# GPIO.net
KiCad netlist of a schematic drawn in Altium Designer
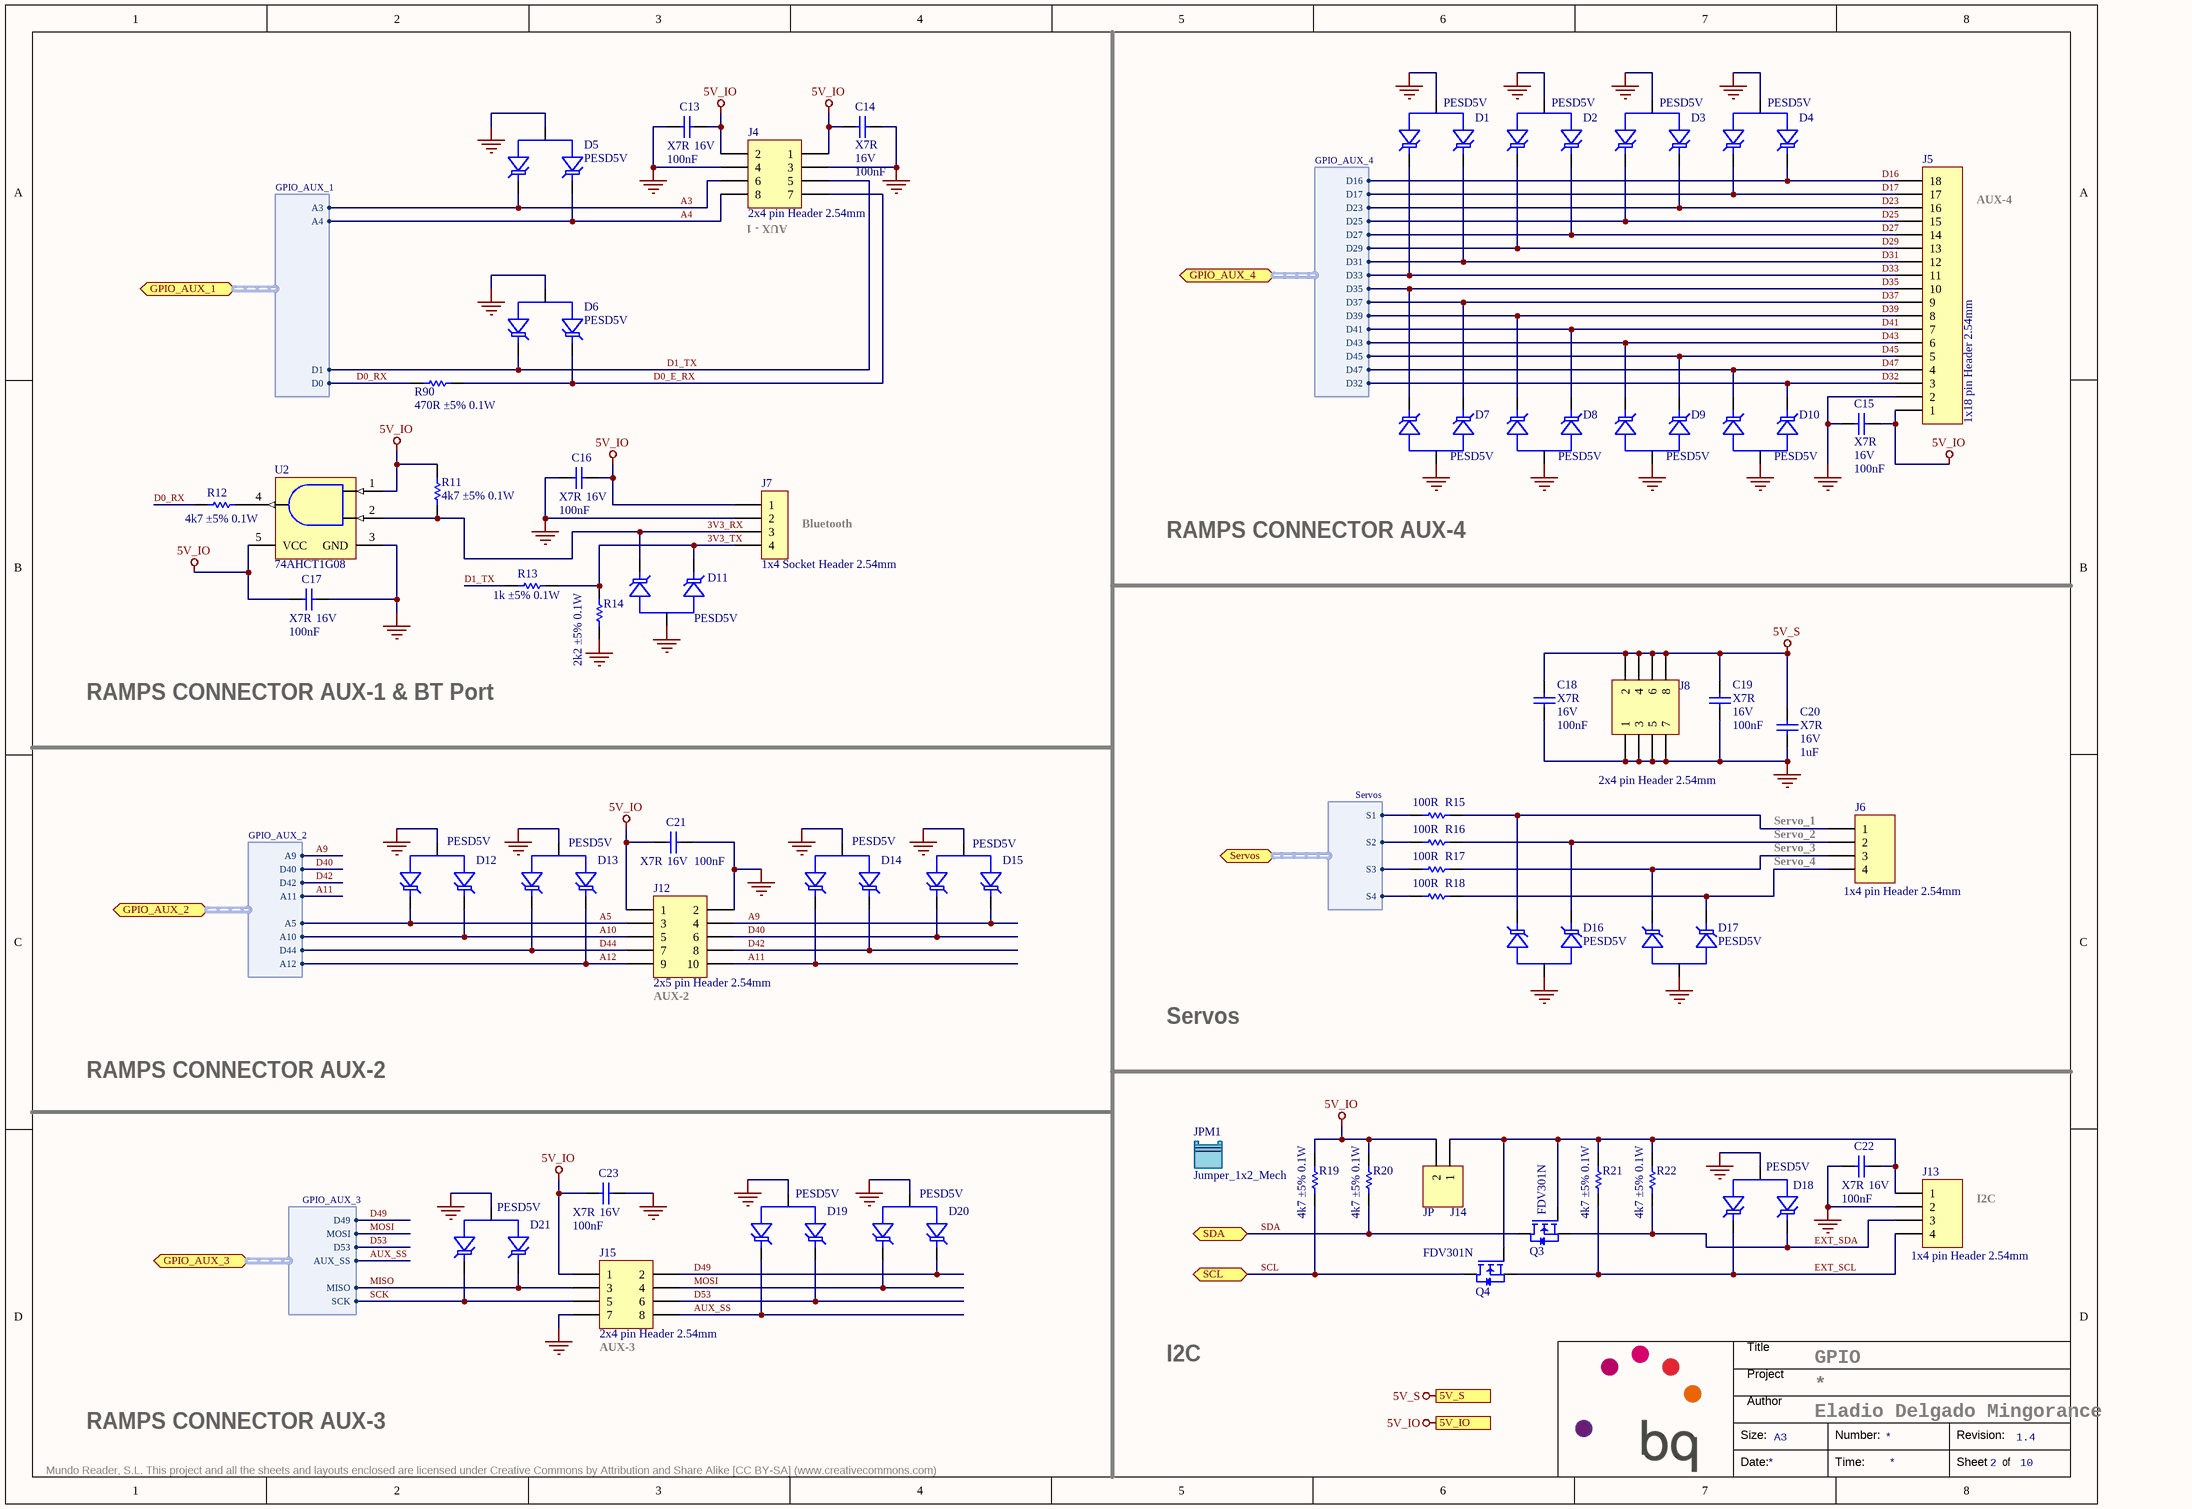
[diagram p0: GPIO.SchDoc]

(export (version "E")
  (design (tool "Eeschema 10.0.6"))
  (components
    (comp (ref "C13")
      (value "Capacitor")
      (footprint "C0603")
      (fields
        (field (name "DIELECTRIC") "X7R")
        (field (name "VOLTAGE") "16V")
        (field (name "CAPACITANCE") "100nF")
        (field (name "PART NUMBER") "C0603_100nF_16V_±10%")
        (field (name "TOLERANCE") "±10%")
        (field (name "MANUFACTURER") "Kemet")
      )
      (libsource (lib "Pasives_Capacitor_SMD") (part "Capacitor"))
    )
    (comp (ref "C14")
      (value "Capacitor")
      (footprint "C0603")
      (fields
        (field (name "DIELECTRIC") "X7R")
        (field (name "VOLTAGE") "16V")
        (field (name "CAPACITANCE") "100nF")
        (field (name "PART NUMBER") "C0603_100nF_16V_±10%")
        (field (name "TOLERANCE") "±10%")
        (field (name "MANUFACTURER") "Kemet")
      )
      (libsource (lib "Pasives_Capacitor_SMD") (part "Capacitor"))
    )
    (comp (ref "C15")
      (value "Capacitor")
      (footprint "C0603")
      (fields
        (field (name "DIELECTRIC") "X7R")
        (field (name "VOLTAGE") "16V")
        (field (name "CAPACITANCE") "100nF")
        (field (name "PART NUMBER") "C0603_100nF_16V_±10%")
        (field (name "TOLERANCE") "±10%")
        (field (name "MANUFACTURER") "Kemet")
      )
      (libsource (lib "Pasives_Capacitor_SMD") (part "Capacitor"))
    )
    (comp (ref "C16")
      (value "Capacitor")
      (footprint "C0603")
      (fields
        (field (name "DIELECTRIC") "X7R")
        (field (name "VOLTAGE") "16V")
        (field (name "CAPACITANCE") "100nF")
        (field (name "PART NUMBER") "C0603_100nF_16V_±10%")
        (field (name "TOLERANCE") "±10%")
        (field (name "MANUFACTURER") "Kemet")
      )
      (libsource (lib "Pasives_Capacitor_SMD") (part "Capacitor"))
    )
    (comp (ref "C17")
      (value "Capacitor")
      (footprint "C0603")
      (fields
        (field (name "DIELECTRIC") "X7R")
        (field (name "VOLTAGE") "16V")
        (field (name "CAPACITANCE") "100nF")
        (field (name "PART NUMBER") "C0603_100nF_16V_±10%")
        (field (name "TOLERANCE") "±10%")
        (field (name "MANUFACTURER") "Kemet")
      )
      (libsource (lib "Pasives_Capacitor_SMD") (part "Capacitor"))
    )
    (comp (ref "C18")
      (value "Capacitor")
      (footprint "C0603")
      (fields
        (field (name "DIELECTRIC") "X7R")
        (field (name "VOLTAGE") "16V")
        (field (name "CAPACITANCE") "100nF")
        (field (name "PART NUMBER") "C0603_100nF_16V_±10%")
        (field (name "TOLERANCE") "±10%")
        (field (name "MANUFACTURER") "Kemet")
      )
      (libsource (lib "Pasives_Capacitor_SMD") (part "Capacitor"))
    )
    (comp (ref "C19")
      (value "Capacitor")
      (footprint "C0603")
      (fields
        (field (name "DIELECTRIC") "X7R")
        (field (name "VOLTAGE") "16V")
        (field (name "CAPACITANCE") "100nF")
        (field (name "PART NUMBER") "C0603_100nF_16V_±10%")
        (field (name "TOLERANCE") "±10%")
        (field (name "MANUFACTURER") "Kemet")
      )
      (libsource (lib "Pasives_Capacitor_SMD") (part "Capacitor"))
    )
    (comp (ref "C20")
      (value "Capacitor")
      (footprint "C0603")
      (fields
        (field (name "DIELECTRIC") "X7R")
        (field (name "VOLTAGE") "16V")
        (field (name "CAPACITANCE") "1uF")
        (field (name "PART NUMBER") "C0603_1uF_16V_±10%_X7R")
        (field (name "TOLERANCE") "±10%")
        (field (name "MANUFACTURER") "TDK")
      )
      (libsource (lib "Pasives_Capacitor_SMD") (part "Capacitor"))
    )
    (comp (ref "C21")
      (value "Capacitor")
      (footprint "C0603")
      (fields
        (field (name "DIELECTRIC") "X7R")
        (field (name "VOLTAGE") "16V")
        (field (name "CAPACITANCE") "100nF")
        (field (name "PART NUMBER") "C0603_100nF_16V_±10%")
        (field (name "TOLERANCE") "±10%")
        (field (name "MANUFACTURER") "Kemet")
      )
      (libsource (lib "Pasives_Capacitor_SMD") (part "Capacitor"))
    )
    (comp (ref "C22")
      (value "Capacitor")
      (footprint "C0603")
      (fields
        (field (name "DIELECTRIC") "X7R")
        (field (name "VOLTAGE") "16V")
        (field (name "CAPACITANCE") "100nF")
        (field (name "PART NUMBER") "C0603_100nF_16V_±10%")
        (field (name "TOLERANCE") "±10%")
        (field (name "MANUFACTURER") "Kemet")
      )
      (libsource (lib "Pasives_Capacitor_SMD") (part "Capacitor"))
    )
    (comp (ref "C23")
      (value "Capacitor")
      (footprint "C0603")
      (fields
        (field (name "DIELECTRIC") "X7R")
        (field (name "VOLTAGE") "16V")
        (field (name "CAPACITANCE") "100nF")
        (field (name "PART NUMBER") "C0603_100nF_16V_±10%")
        (field (name "TOLERANCE") "±10%")
        (field (name "MANUFACTURER") "Kemet")
      )
      (libsource (lib "Pasives_Capacitor_SMD") (part "Capacitor"))
    )
    (comp (ref "D1")
      (value "PESD5V")
      (footprint "SOT323_3_SC70")
      (description "Dual ESD protection diode")
      (fields (field (name "MANUFACTURER") "NXP"))
      (libsource (lib "Protection") (part "ESD_Dual_Diode"))
    )
    (comp (ref "D2")
      (value "PESD5V")
      (footprint "SOT323_3_SC70")
      (description "Dual ESD protection diode")
      (fields (field (name "MANUFACTURER") "NXP"))
      (libsource (lib "Protection") (part "ESD_Dual_Diode"))
    )
    (comp (ref "D3")
      (value "PESD5V")
      (footprint "SOT323_3_SC70")
      (description "Dual ESD protection diode")
      (fields (field (name "MANUFACTURER") "NXP"))
      (libsource (lib "Protection") (part "ESD_Dual_Diode"))
    )
    (comp (ref "D4")
      (value "PESD5V")
      (footprint "SOT323_3_SC70")
      (description "Dual ESD protection diode")
      (fields (field (name "MANUFACTURER") "NXP"))
      (libsource (lib "Protection") (part "ESD_Dual_Diode"))
    )
    (comp (ref "D5")
      (value "PESD5V")
      (footprint "SOT323_3_SC70")
      (description "Dual ESD protection diode")
      (fields (field (name "MANUFACTURER") "NXP"))
      (libsource (lib "Protection") (part "ESD_Dual_Diode"))
    )
    (comp (ref "D6")
      (value "PESD5V")
      (footprint "SOT323_3_SC70")
      (description "Dual ESD protection diode")
      (fields (field (name "MANUFACTURER") "NXP"))
      (libsource (lib "Protection") (part "ESD_Dual_Diode"))
    )
    (comp (ref "D7")
      (value "PESD5V")
      (footprint "SOT323_3_SC70")
      (description "Dual ESD protection diode")
      (fields (field (name "MANUFACTURER") "NXP"))
      (libsource (lib "Protection") (part "ESD_Dual_Diode"))
    )
    (comp (ref "D8")
      (value "PESD5V")
      (footprint "SOT323_3_SC70")
      (description "Dual ESD protection diode")
      (fields (field (name "MANUFACTURER") "NXP"))
      (libsource (lib "Protection") (part "ESD_Dual_Diode"))
    )
    (comp (ref "D9")
      (value "PESD5V")
      (footprint "SOT323_3_SC70")
      (description "Dual ESD protection diode")
      (fields (field (name "MANUFACTURER") "NXP"))
      (libsource (lib "Protection") (part "ESD_Dual_Diode"))
    )
    (comp (ref "D10")
      (value "PESD5V")
      (footprint "SOT323_3_SC70")
      (description "Dual ESD protection diode")
      (fields (field (name "MANUFACTURER") "NXP"))
      (libsource (lib "Protection") (part "ESD_Dual_Diode"))
    )
    (comp (ref "D11")
      (value "PESD5V")
      (footprint "SOT323_3_SC70")
      (description "Dual ESD protection diode")
      (fields (field (name "MANUFACTURER") "NXP"))
      (libsource (lib "Protection") (part "ESD_Dual_Diode"))
    )
    (comp (ref "D12")
      (value "PESD5V")
      (footprint "SOT323_3_SC70")
      (description "Dual ESD protection diode")
      (fields (field (name "MANUFACTURER") "NXP"))
      (libsource (lib "Protection") (part "ESD_Dual_Diode"))
    )
    (comp (ref "D13")
      (value "PESD5V")
      (footprint "SOT323_3_SC70")
      (description "Dual ESD protection diode")
      (fields (field (name "MANUFACTURER") "NXP"))
      (libsource (lib "Protection") (part "ESD_Dual_Diode"))
    )
    (comp (ref "D14")
      (value "PESD5V")
      (footprint "SOT323_3_SC70")
      (description "Dual ESD protection diode")
      (fields (field (name "MANUFACTURER") "NXP"))
      (libsource (lib "Protection") (part "ESD_Dual_Diode"))
    )
    (comp (ref "D15")
      (value "PESD5V")
      (footprint "SOT323_3_SC70")
      (description "Dual ESD protection diode")
      (fields (field (name "MANUFACTURER") "NXP"))
      (libsource (lib "Protection") (part "ESD_Dual_Diode"))
    )
    (comp (ref "D16")
      (value "PESD5V")
      (footprint "SOT323_3_SC70")
      (description "Dual ESD protection diode")
      (fields (field (name "MANUFACTURER") "NXP"))
      (libsource (lib "Protection") (part "ESD_Dual_Diode"))
    )
    (comp (ref "D17")
      (value "PESD5V")
      (footprint "SOT323_3_SC70")
      (description "Dual ESD protection diode")
      (fields (field (name "MANUFACTURER") "NXP"))
      (libsource (lib "Protection") (part "ESD_Dual_Diode"))
    )
    (comp (ref "D18")
      (value "PESD5V")
      (footprint "SOT323_3_SC70")
      (description "Dual ESD protection diode")
      (fields (field (name "MANUFACTURER") "NXP"))
      (libsource (lib "Protection") (part "ESD_Dual_Diode"))
    )
    (comp (ref "D19")
      (value "PESD5V")
      (footprint "SOT323_3_SC70")
      (description "Dual ESD protection diode")
      (fields (field (name "MANUFACTURER") "NXP"))
      (libsource (lib "Protection") (part "ESD_Dual_Diode"))
    )
    (comp (ref "D20")
      (value "PESD5V")
      (footprint "SOT323_3_SC70")
      (description "Dual ESD protection diode")
      (fields (field (name "MANUFACTURER") "NXP"))
      (libsource (lib "Protection") (part "ESD_Dual_Diode"))
    )
    (comp (ref "D21")
      (value "PESD5V")
      (footprint "SOT323_3_SC70")
      (description "Dual ESD protection diode")
      (fields (field (name "MANUFACTURER") "NXP"))
      (libsource (lib "Protection") (part "ESD_Dual_Diode"))
    )
    (comp (ref "J4")
      (value "2x4 pin Header 2.54mm")
      (footprint "2x4 Pin Header 2.54")
      (description "Connector, 8 pin Dual Header 2.54mm")
      (fields (field (name "MANUFACTURER") "Samtec") (field (name "PART NUMBER") "CON_DPH_THT2.54_8"))
      (libsource (lib "") (part "2x4 pin Header 2.54mm_2"))
    )
    (comp (ref "J5")
      (value "1x18 pin Header 2.54mm")
      (footprint "1x18 Pin Header 2.54")
      (fields (field (name "MANUFACTURER") "Samtec") (field (name "PART NUMBER") "CON_PH_THT2.54_18"))
      (libsource (lib "Conectores_PinHeader_2.54") (part "1x18 pin Header 2.54mm"))
    )
    (comp (ref "J6")
      (value "1x4 pin Header 2.54mm")
      (footprint "1x4 Pin Header 2.54")
      (fields (field (name "MANUFACTURER") "Samtec") (field (name "PART NUMBER") "CON_PH_THT2.54_4"))
      (libsource (lib "Conectores_PinHeader_2.54") (part "1x4 pin Header 2.54mm"))
    )
    (comp (ref "J7")
      (value "1x4 Socket Header 2.54mm")
      (footprint "1x4 Socket Header THT 2.54mm")
      (description "4 pin Socket Header 2.54mm")
      (fields (field (name "PART NUMBER") "CON_SH_THT2.54_4") (field (name "MANUFACTURER") "Samtec"))
      (libsource (lib "Conectores_SocketHeader_2.54") (part "1x4 Socket Header 2.54mm"))
    )
    (comp (ref "J8")
      (value "2x4 pin Header 2.54mm")
      (footprint "2x4 Pin Header 2.54")
      (description "Connector, 8 pin Dual Header 2.54mm")
      (fields (field (name "MANUFACTURER") "Samtec") (field (name "PART NUMBER") "CON_DPH_THT2.54_8"))
      (libsource (lib "") (part "2x4 pin Header 2.54mm_1"))
    )
    (comp (ref "J12")
      (value "2x5 pin Header 2.54mm")
      (footprint "2x5 Pin Header 2.54")
      (description "10 pin Dual Header 2.54mm")
      (fields (field (name "MANUFACTURER") "Samtec") (field (name "PART NUMBER") "CON_DPH_THT2.54_10"))
      (libsource (lib "Conectores_PinHeader_2.54") (part "2x5 pin Header 2.54mm"))
    )
    (comp (ref "J13")
      (value "1x4 pin Header 2.54mm")
      (footprint "1x4 Pin Header 2.54")
      (fields (field (name "MANUFACTURER") "Samtec") (field (name "PART NUMBER") "CON_PH_THT2.54_4"))
      (libsource (lib "Conectores_PinHeader_2.54") (part "1x4 pin Header 2.54mm"))
    )
    (comp (ref "J14")
      (value "JP")
      (footprint "1x2 Pin Header 2.54")
      (description "1x2 pin Header 2.54mm")
      (fields (field (name "PART NUMBER") "CON_PH_THT2.54_2") (field (name "MANUFACTURER") "Samtec"))
      (libsource (lib "Conectores_PinHeader_2.54") (part "1x2 pin Header 2.54mm"))
    )
    (comp (ref "J15")
      (value "2x4 pin Header 2.54mm")
      (footprint "2x4 Pin Header 2.54")
      (description "8 pin Dual Header 2.54mm")
      (fields (field (name "MANUFACTURER") "Samtec") (field (name "PART NUMBER") "CON_DPH_THT2.54_8"))
      (libsource (lib "Conectores_PinHeader_2.54") (part "2x4 pin Header 2.54mm"))
    )
    (comp (ref "JPM1")
      (value "Jumper_1x2_Mech")
      (description "Connector, Jumper, 1x2 Jumper 2.54mm")
      (fields (field (name "PART NUMBER") "Jumper_2pin_Mech") (field (name "MANUFACTURER") "Würth"))
      (libsource (lib "Connectors_Jumpers") (part "Jumper_1x2_Mech"))
    )
    (comp (ref "Q3")
      (value "FDV301N")
      (footprint "SOT23-3")
      (description "Mosfet Channel N Enhancement Mode")
      (fields (field (name "MANUFACTURER") "Fairchild Semiconductor"))
      (libsource (lib "Semiconductors_Transistors") (part "Mosfet_N"))
    )
    (comp (ref "Q4")
      (value "FDV301N")
      (footprint "SOT23-3")
      (description "Mosfet Channel N Enhancement Mode")
      (fields (field (name "MANUFACTURER") "Fairchild Semiconductor"))
      (libsource (lib "Semiconductors_Transistors") (part "Mosfet_N"))
    )
    (comp (ref "R11")
      (value "4k7 ±5% 0.1W")
      (footprint "R0603")
      (description "Resistor, SMD")
      (fields (field (name "TOLERANCE") "±5%") (field (name "POWER") "0.1W"))
      (libsource (lib "Pasives_Resistor_SMD") (part "Resistor"))
    )
    (comp (ref "R12")
      (value "4k7 ±5% 0.1W")
      (footprint "R0603")
      (description "Resistor")
      (fields (field (name "TOLERANCE") "±5%") (field (name "POWER") "0.1W"))
      (libsource (lib "Pasives_Resistor_SMD") (part "Resistor"))
    )
    (comp (ref "R13")
      (value "1k ±5% 0.1W")
      (footprint "R0603")
      (description "Resistor")
      (fields (field (name "TOLERANCE") "±5%") (field (name "POWER") "0.1W"))
      (libsource (lib "Pasives_Resistor_SMD") (part "Resistor"))
    )
    (comp (ref "R14")
      (value "2k2 ±5% 0.1W")
      (footprint "R0603")
      (description "Resistor")
      (fields (field (name "TOLERANCE") "±5%") (field (name "POWER") "0.1W"))
      (libsource (lib "Pasives_Resistor_SMD") (part "Resistor"))
    )
    (comp (ref "R15")
      (value "~")
      (footprint "R0603")
      (description "Resistor")
      (fields
        (field (name "TOLERANCE") "±5%")
        (field (name "POWER") "0.1W")
        (field (name "RESISTANCE") "100R")
      )
      (libsource (lib "Pasives_Resistor_SMD") (part "Resistor"))
    )
    (comp (ref "R16")
      (value "~")
      (footprint "R0603")
      (description "Resistor")
      (fields
        (field (name "TOLERANCE") "±5%")
        (field (name "POWER") "0.1W")
        (field (name "RESISTANCE") "100R")
      )
      (libsource (lib "Pasives_Resistor_SMD") (part "Resistor"))
    )
    (comp (ref "R17")
      (value "~")
      (footprint "R0603")
      (description "Resistor")
      (fields
        (field (name "TOLERANCE") "±5%")
        (field (name "POWER") "0.1W")
        (field (name "RESISTANCE") "100R")
      )
      (libsource (lib "Pasives_Resistor_SMD") (part "Resistor"))
    )
    (comp (ref "R18")
      (value "~")
      (footprint "R0603")
      (description "Resistor")
      (fields
        (field (name "TOLERANCE") "±5%")
        (field (name "POWER") "0.1W")
        (field (name "RESISTANCE") "100R")
      )
      (libsource (lib "Pasives_Resistor_SMD") (part "Resistor"))
    )
    (comp (ref "R19")
      (value "4k7 ±5% 0.1W")
      (footprint "R0603")
      (description "Resistor")
      (fields (field (name "TOLERANCE") "±5%") (field (name "POWER") "0.1W"))
      (libsource (lib "Pasives_Resistor_SMD") (part "Resistor"))
    )
    (comp (ref "R20")
      (value "4k7 ±5% 0.1W")
      (footprint "R0603")
      (description "Resistor")
      (fields (field (name "TOLERANCE") "±5%") (field (name "POWER") "0.1W"))
      (libsource (lib "Pasives_Resistor_SMD") (part "Resistor"))
    )
    (comp (ref "R21")
      (value "4k7 ±5% 0.1W")
      (footprint "R0603")
      (description "Resistor")
      (fields (field (name "TOLERANCE") "±5%") (field (name "POWER") "0.1W"))
      (libsource (lib "Pasives_Resistor_SMD") (part "Resistor"))
    )
    (comp (ref "R22")
      (value "4k7 ±5% 0.1W")
      (footprint "R0603")
      (description "Resistor")
      (fields (field (name "TOLERANCE") "±5%") (field (name "POWER") "0.1W"))
      (libsource (lib "Pasives_Resistor_SMD") (part "Resistor"))
    )
    (comp (ref "R90")
      (value "470R ±5% 0.1W")
      (footprint "R0603")
      (description "Resistor, SMD")
      (fields (field (name "TOLERANCE") "±5%") (field (name "POWER") "0.1W"))
      (libsource (lib "Pasives_Resistor_SMD") (part "Resistor"))
    )
    (comp (ref "U2")
      (value "74AHCT1G08")
      (footprint "SOT23-5")
      (description "Dual AND Gate Single Ouput")
      (fields (field (name "PART NUMBER") "SN74AHCT1G08") (field (name "MANUFACTURER") "Texas Instruments"))
      (libsource (lib "Semiconductors_Logic_Gate") (part "AND_2I_1O"))
    )
  )
  (nets
    (net (code "6") (name "/3V3_RX") (class "Default")
      (node (ref "D11") (pin "2") (pinfunction "2_2") (pintype "passive"))
      (node (ref "J7") (pin "3") (pinfunction "3_3") (pintype "passive"))
      (node (ref "R11") (pin "1") (pinfunction "1_1") (pintype "passive"))
      (node (ref "U2") (pin "2") (pinfunction "B_2") (pintype "input"))
    )
    (net (code "7") (name "/3V3_TX") (class "Default")
      (node (ref "D11") (pin "1") (pinfunction "1_1") (pintype "passive"))
      (node (ref "J7") (pin "4") (pinfunction "4_4") (pintype "passive"))
      (node (ref "R13") (pin "2") (pinfunction "2_2") (pintype "passive"))
      (node (ref "R14") (pin "2") (pinfunction "2_2") (pintype "passive"))
    )
    (net (code "8") (name "/A3") (class "Default")
      (node (ref "D5") (pin "1") (pinfunction "1_1") (pintype "passive"))
      (node (ref "J4") (pin "6") (pinfunction "6_6") (pintype "passive"))
    )
    (net (code "9") (name "/A4") (class "Default")
      (node (ref "D5") (pin "2") (pinfunction "2_2") (pintype "passive"))
      (node (ref "J4") (pin "8") (pinfunction "8_8") (pintype "passive"))
    )
    (net (code "10") (name "/A5") (class "Default")
      (node (ref "D12") (pin "2") (pinfunction "2_2") (pintype "passive"))
      (node (ref "J12") (pin "3") (pinfunction "3_3") (pintype "passive"))
    )
    (net (code "11") (name "/A9") (class "Default")
      (node (ref "D15") (pin "1") (pinfunction "1_1") (pintype "passive"))
      (node (ref "J12") (pin "4") (pinfunction "4_4") (pintype "passive"))
    )
    (net (code "12") (name "/A10") (class "Default")
      (node (ref "D12") (pin "1") (pinfunction "1_1") (pintype "passive"))
      (node (ref "J12") (pin "5") (pinfunction "5_5") (pintype "passive"))
    )
    (net (code "13") (name "/A11") (class "Default")
      (node (ref "D14") (pin "2") (pinfunction "2_2") (pintype "passive"))
      (node (ref "J12") (pin "10") (pinfunction "10_10") (pintype "passive"))
    )
    (net (code "14") (name "/A12") (class "Default")
      (node (ref "D13") (pin "1") (pinfunction "1_1") (pintype "passive"))
      (node (ref "J12") (pin "9") (pinfunction "9_9") (pintype "passive"))
    )
    (net (code "15") (name "/AUX_SS") (class "Default")
      (node (ref "D19") (pin "2") (pinfunction "2_2") (pintype "passive"))
      (node (ref "J15") (pin "8") (pinfunction "8_8") (pintype "passive"))
    )
    (net (code "16") (name "/D0_E_RX") (class "Default")
      (node (ref "D6") (pin "1") (pinfunction "1_1") (pintype "passive"))
      (node (ref "J4") (pin "7") (pinfunction "7_7") (pintype "passive"))
      (node (ref "R90") (pin "1") (pinfunction "1_1") (pintype "passive"))
    )
    (net (code "17") (name "/D0_RX") (class "Default")
      (node (ref "R12") (pin "2") (pinfunction "2_2") (pintype "passive"))
      (node (ref "R90") (pin "2") (pinfunction "2_2") (pintype "passive"))
    )
    (net (code "18") (name "/D1_TX") (class "Default")
      (node (ref "D6") (pin "2") (pinfunction "2_2") (pintype "passive"))
      (node (ref "J4") (pin "5") (pinfunction "5_5") (pintype "passive"))
      (node (ref "R13") (pin "1") (pinfunction "1_1") (pintype "passive"))
    )
    (net (code "19") (name "/D16") (class "Default")
      (node (ref "D4") (pin "2") (pinfunction "2_2") (pintype "passive"))
      (node (ref "J5") (pin "18") (pinfunction "18_18") (pintype "passive"))
    )
    (net (code "20") (name "/D17") (class "Default")
      (node (ref "D4") (pin "1") (pinfunction "1_1") (pintype "passive"))
      (node (ref "J5") (pin "17") (pinfunction "17_17") (pintype "passive"))
    )
    (net (code "21") (name "/D23") (class "Default")
      (node (ref "D3") (pin "2") (pinfunction "2_2") (pintype "passive"))
      (node (ref "J5") (pin "16") (pinfunction "16_16") (pintype "passive"))
    )
    (net (code "22") (name "/D25") (class "Default")
      (node (ref "D3") (pin "1") (pinfunction "1_1") (pintype "passive"))
      (node (ref "J5") (pin "15") (pinfunction "15_15") (pintype "passive"))
    )
    (net (code "23") (name "/D27") (class "Default")
      (node (ref "D2") (pin "2") (pinfunction "2_2") (pintype "passive"))
      (node (ref "J5") (pin "14") (pinfunction "14_14") (pintype "passive"))
    )
    (net (code "24") (name "/D29") (class "Default")
      (node (ref "D2") (pin "1") (pinfunction "1_1") (pintype "passive"))
      (node (ref "J5") (pin "13") (pinfunction "13_13") (pintype "passive"))
    )
    (net (code "25") (name "/D31") (class "Default")
      (node (ref "D1") (pin "2") (pinfunction "2_2") (pintype "passive"))
      (node (ref "J5") (pin "12") (pinfunction "12_12") (pintype "passive"))
    )
    (net (code "26") (name "/D32") (class "Default")
      (node (ref "D10") (pin "1") (pinfunction "1_1") (pintype "passive"))
      (node (ref "J5") (pin "3") (pinfunction "3_3") (pintype "passive"))
    )
    (net (code "27") (name "/D33") (class "Default")
      (node (ref "D1") (pin "1") (pinfunction "1_1") (pintype "passive"))
      (node (ref "J5") (pin "11") (pinfunction "11_11") (pintype "passive"))
    )
    (net (code "28") (name "/D35") (class "Default")
      (node (ref "D7") (pin "2") (pinfunction "2_2") (pintype "passive"))
      (node (ref "J5") (pin "10") (pinfunction "10_10") (pintype "passive"))
    )
    (net (code "29") (name "/D37") (class "Default")
      (node (ref "D7") (pin "1") (pinfunction "1_1") (pintype "passive"))
      (node (ref "J5") (pin "9") (pinfunction "9_9") (pintype "passive"))
    )
    (net (code "30") (name "/D39") (class "Default")
      (node (ref "D8") (pin "2") (pinfunction "2_2") (pintype "passive"))
      (node (ref "J5") (pin "8") (pinfunction "8_8") (pintype "passive"))
    )
    (net (code "31") (name "/D40") (class "Default")
      (node (ref "D15") (pin "2") (pinfunction "2_2") (pintype "passive"))
      (node (ref "J12") (pin "6") (pinfunction "6_6") (pintype "passive"))
    )
    (net (code "32") (name "/D41") (class "Default")
      (node (ref "D8") (pin "1") (pinfunction "1_1") (pintype "passive"))
      (node (ref "J5") (pin "7") (pinfunction "7_7") (pintype "passive"))
    )
    (net (code "33") (name "/D42") (class "Default")
      (node (ref "D14") (pin "1") (pinfunction "1_1") (pintype "passive"))
      (node (ref "J12") (pin "8") (pinfunction "8_8") (pintype "passive"))
    )
    (net (code "34") (name "/D43") (class "Default")
      (node (ref "D9") (pin "2") (pinfunction "2_2") (pintype "passive"))
      (node (ref "J5") (pin "6") (pinfunction "6_6") (pintype "passive"))
    )
    (net (code "35") (name "/D44") (class "Default")
      (node (ref "D13") (pin "2") (pinfunction "2_2") (pintype "passive"))
      (node (ref "J12") (pin "7") (pinfunction "7_7") (pintype "passive"))
    )
    (net (code "36") (name "/D45") (class "Default")
      (node (ref "D9") (pin "1") (pinfunction "1_1") (pintype "passive"))
      (node (ref "J5") (pin "5") (pinfunction "5_5") (pintype "passive"))
    )
    (net (code "37") (name "/D47") (class "Default")
      (node (ref "D10") (pin "2") (pinfunction "2_2") (pintype "passive"))
      (node (ref "J5") (pin "4") (pinfunction "4_4") (pintype "passive"))
    )
    (net (code "38") (name "/D49") (class "Default")
      (node (ref "D20") (pin "1") (pinfunction "1_1") (pintype "passive"))
      (node (ref "J15") (pin "2") (pinfunction "2_2") (pintype "passive"))
    )
    (net (code "39") (name "/D53") (class "Default")
      (node (ref "D19") (pin "1") (pinfunction "1_1") (pintype "passive"))
      (node (ref "J15") (pin "6") (pinfunction "6_6") (pintype "passive"))
    )
    (net (code "40") (name "/EXT_SCL") (class "Default")
      (node (ref "D18") (pin "1") (pinfunction "1_1") (pintype "passive"))
      (node (ref "J13") (pin "4") (pinfunction "4_4") (pintype "passive"))
      (node (ref "Q4") (pin "2") (pinfunction "S_2") (pintype "passive"))
      (node (ref "R21") (pin "2") (pinfunction "2_2") (pintype "passive"))
    )
    (net (code "41") (name "/EXT_SDA") (class "Default")
      (node (ref "D18") (pin "2") (pinfunction "2_2") (pintype "passive"))
      (node (ref "J13") (pin "3") (pinfunction "3_3") (pintype "passive"))
      (node (ref "Q3") (pin "2") (pinfunction "S_2") (pintype "passive"))
      (node (ref "R22") (pin "2") (pinfunction "2_2") (pintype "passive"))
    )
    (net (code "42") (name "/MISO") (class "Default")
      (node (ref "D21") (pin "2") (pinfunction "2_2") (pintype "passive"))
      (node (ref "J15") (pin "3") (pinfunction "3_3") (pintype "passive"))
    )
    (net (code "43") (name "/MOSI") (class "Default")
      (node (ref "D20") (pin "2") (pinfunction "2_2") (pintype "passive"))
      (node (ref "J15") (pin "4") (pinfunction "4_4") (pintype "passive"))
    )
    (net (code "44") (name "/S1") (class "Default")
      (node (ref "R15") (pin "1") (pinfunction "1_1") (pintype "passive"))
    )
    (net (code "45") (name "/S2") (class "Default")
      (node (ref "R16") (pin "1") (pinfunction "1_1") (pintype "passive"))
    )
    (net (code "46") (name "/S3") (class "Default")
      (node (ref "R17") (pin "1") (pinfunction "1_1") (pintype "passive"))
    )
    (net (code "47") (name "/S4") (class "Default")
      (node (ref "R18") (pin "1") (pinfunction "1_1") (pintype "passive"))
    )
    (net (code "48") (name "/SCK") (class "Default")
      (node (ref "D21") (pin "1") (pinfunction "1_1") (pintype "passive"))
      (node (ref "J15") (pin "5") (pinfunction "5_5") (pintype "passive"))
    )
    (net (code "49") (name "/SCL") (class "Default")
      (node (ref "Q4") (pin "3") (pinfunction "D_3") (pintype "passive"))
      (node (ref "R19") (pin "2") (pinfunction "2_2") (pintype "passive"))
    )
    (net (code "50") (name "/SDA") (class "Default")
      (node (ref "Q3") (pin "3") (pinfunction "D_3") (pintype "passive"))
      (node (ref "R20") (pin "2") (pinfunction "2_2") (pintype "passive"))
    )
    (net (code "56") (name "5V_IO") (class "Default")
      (node (ref "C13") (pin "1") (pinfunction "1_1") (pintype "passive"))
      (node (ref "C14") (pin "1") (pinfunction "1_1") (pintype "passive"))
      (node (ref "C15") (pin "1") (pinfunction "1_1") (pintype "passive"))
      (node (ref "C16") (pin "1") (pinfunction "1_1") (pintype "passive"))
      (node (ref "C17") (pin "2") (pinfunction "2_2") (pintype "passive"))
      (node (ref "C21") (pin "2") (pinfunction "2_2") (pintype "passive"))
      (node (ref "C23") (pin "2") (pinfunction "2_2") (pintype "passive"))
      (node (ref "J12") (pin "1") (pinfunction "1_1") (pintype "passive"))
      (node (ref "J14") (pin "2") (pinfunction "2_2") (pintype "passive"))
      (node (ref "J15") (pin "1") (pinfunction "1_1") (pintype "passive"))
      (node (ref "J4") (pin "1") (pinfunction "1_1") (pintype "passive"))
      (node (ref "J4") (pin "2") (pinfunction "2_2") (pintype "passive"))
      (node (ref "J5") (pin "1") (pinfunction "1_1") (pintype "passive"))
      (node (ref "J7") (pin "1") (pinfunction "1_1") (pintype "passive"))
      (node (ref "R11") (pin "2") (pinfunction "2_2") (pintype "passive"))
      (node (ref "R19") (pin "1") (pinfunction "1_1") (pintype "passive"))
      (node (ref "R20") (pin "1") (pinfunction "1_1") (pintype "passive"))
      (node (ref "U2") (pin "1") (pinfunction "A_1") (pintype "input"))
      (node (ref "U2") (pin "5") (pinfunction "VCC_5") (pintype "power_in"))
    )
    (net (code "57") (name "5V_S") (class "Default")
      (node (ref "C18") (pin "2") (pinfunction "2_2") (pintype "passive"))
      (node (ref "C19") (pin "2") (pinfunction "2_2") (pintype "passive"))
      (node (ref "C20") (pin "2") (pinfunction "2_2") (pintype "passive"))
      (node (ref "J8") (pin "2") (pinfunction "2_2") (pintype "passive"))
      (node (ref "J8") (pin "4") (pinfunction "4_4") (pintype "passive"))
      (node (ref "J8") (pin "6") (pinfunction "6_6") (pintype "passive"))
      (node (ref "J8") (pin "8") (pinfunction "8_8") (pintype "passive"))
    )
    (net (code "58") (name "GND") (class "Default")
      (node (ref "C13") (pin "2") (pinfunction "2_2") (pintype "passive"))
      (node (ref "C14") (pin "2") (pinfunction "2_2") (pintype "passive"))
      (node (ref "C15") (pin "2") (pinfunction "2_2") (pintype "passive"))
      (node (ref "C16") (pin "2") (pinfunction "2_2") (pintype "passive"))
      (node (ref "C17") (pin "1") (pinfunction "1_1") (pintype "passive"))
      (node (ref "C18") (pin "1") (pinfunction "1_1") (pintype "passive"))
      (node (ref "C19") (pin "1") (pinfunction "1_1") (pintype "passive"))
      (node (ref "C20") (pin "1") (pinfunction "1_1") (pintype "passive"))
      (node (ref "C21") (pin "1") (pinfunction "1_1") (pintype "passive"))
      (node (ref "C22") (pin "2") (pinfunction "2_2") (pintype "passive"))
      (node (ref "C23") (pin "1") (pinfunction "1_1") (pintype "passive"))
      (node (ref "D1") (pin "3") (pinfunction "3_3") (pintype "passive"))
      (node (ref "D10") (pin "3") (pinfunction "3_3") (pintype "passive"))
      (node (ref "D11") (pin "3") (pinfunction "3_3") (pintype "passive"))
      (node (ref "D12") (pin "3") (pinfunction "3_3") (pintype "passive"))
      (node (ref "D13") (pin "3") (pinfunction "3_3") (pintype "passive"))
      (node (ref "D14") (pin "3") (pinfunction "3_3") (pintype "passive"))
      (node (ref "D15") (pin "3") (pinfunction "3_3") (pintype "passive"))
      (node (ref "D16") (pin "3") (pinfunction "3_3") (pintype "passive"))
      (node (ref "D17") (pin "3") (pinfunction "3_3") (pintype "passive"))
      (node (ref "D18") (pin "3") (pinfunction "3_3") (pintype "passive"))
      (node (ref "D19") (pin "3") (pinfunction "3_3") (pintype "passive"))
      (node (ref "D2") (pin "3") (pinfunction "3_3") (pintype "passive"))
      (node (ref "D20") (pin "3") (pinfunction "3_3") (pintype "passive"))
      (node (ref "D21") (pin "3") (pinfunction "3_3") (pintype "passive"))
      (node (ref "D3") (pin "3") (pinfunction "3_3") (pintype "passive"))
      (node (ref "D4") (pin "3") (pinfunction "3_3") (pintype "passive"))
      (node (ref "D5") (pin "3") (pinfunction "3_3") (pintype "passive"))
      (node (ref "D6") (pin "3") (pinfunction "3_3") (pintype "passive"))
      (node (ref "D7") (pin "3") (pinfunction "3_3") (pintype "passive"))
      (node (ref "D8") (pin "3") (pinfunction "3_3") (pintype "passive"))
      (node (ref "D9") (pin "3") (pinfunction "3_3") (pintype "passive"))
      (node (ref "J12") (pin "2") (pinfunction "2_2") (pintype "passive"))
      (node (ref "J13") (pin "2") (pinfunction "2_2") (pintype "passive"))
      (node (ref "J15") (pin "7") (pinfunction "7_7") (pintype "passive"))
      (node (ref "J4") (pin "3") (pinfunction "3_3") (pintype "passive"))
      (node (ref "J4") (pin "4") (pinfunction "4_4") (pintype "passive"))
      (node (ref "J5") (pin "2") (pinfunction "2_2") (pintype "passive"))
      (node (ref "J7") (pin "2") (pinfunction "2_2") (pintype "passive"))
      (node (ref "J8") (pin "1") (pinfunction "1_1") (pintype "passive"))
      (node (ref "J8") (pin "3") (pinfunction "3_3") (pintype "passive"))
      (node (ref "J8") (pin "5") (pinfunction "5_5") (pintype "passive"))
      (node (ref "J8") (pin "7") (pinfunction "7_7") (pintype "passive"))
      (node (ref "R14") (pin "1") (pinfunction "1_1") (pintype "passive"))
      (node (ref "U2") (pin "3") (pinfunction "GND_3") (pintype "power_in"))
    )
    (net (code "59") (name "Net-(D16-Pad1)") (class "Default")
      (node (ref "D16") (pin "1") (pinfunction "1_1") (pintype "passive"))
      (node (ref "J6") (pin "1") (pinfunction "1_1") (pintype "passive"))
      (node (ref "R15") (pin "2") (pinfunction "2_2") (pintype "passive"))
    )
    (net (code "60") (name "Net-(D16-Pad2)") (class "Default")
      (node (ref "D16") (pin "2") (pinfunction "2_2") (pintype "passive"))
      (node (ref "J6") (pin "2") (pinfunction "2_2") (pintype "passive"))
      (node (ref "R16") (pin "2") (pinfunction "2_2") (pintype "passive"))
    )
    (net (code "61") (name "Net-(D17-Pad1)") (class "Default")
      (node (ref "D17") (pin "1") (pinfunction "1_1") (pintype "passive"))
      (node (ref "J6") (pin "3") (pinfunction "3_3") (pintype "passive"))
      (node (ref "R17") (pin "2") (pinfunction "2_2") (pintype "passive"))
    )
    (net (code "62") (name "Net-(D17-Pad2)") (class "Default")
      (node (ref "D17") (pin "2") (pinfunction "2_2") (pintype "passive"))
      (node (ref "J6") (pin "4") (pinfunction "4_4") (pintype "passive"))
      (node (ref "R18") (pin "2") (pinfunction "2_2") (pintype "passive"))
    )
    (net (code "63") (name "Net-(Q3-G)") (class "Default")
      (node (ref "C22") (pin "1") (pinfunction "1_1") (pintype "passive"))
      (node (ref "J13") (pin "1") (pinfunction "1_1") (pintype "passive"))
      (node (ref "J14") (pin "1") (pinfunction "1_1") (pintype "passive"))
      (node (ref "Q3") (pin "1") (pinfunction "G_1") (pintype "passive"))
      (node (ref "Q4") (pin "1") (pinfunction "G_1") (pintype "passive"))
      (node (ref "R21") (pin "1") (pinfunction "1_1") (pintype "passive"))
      (node (ref "R22") (pin "1") (pinfunction "1_1") (pintype "passive"))
    )
    (net (code "64") (name "Net-(U2-Y)") (class "Default")
      (node (ref "R12") (pin "1") (pinfunction "1_1") (pintype "passive"))
      (node (ref "U2") (pin "4") (pinfunction "Y_4") (pintype "output"))
    )
  )
)
